# Power.net
KiCad netlist of a schematic drawn in Altium Designer
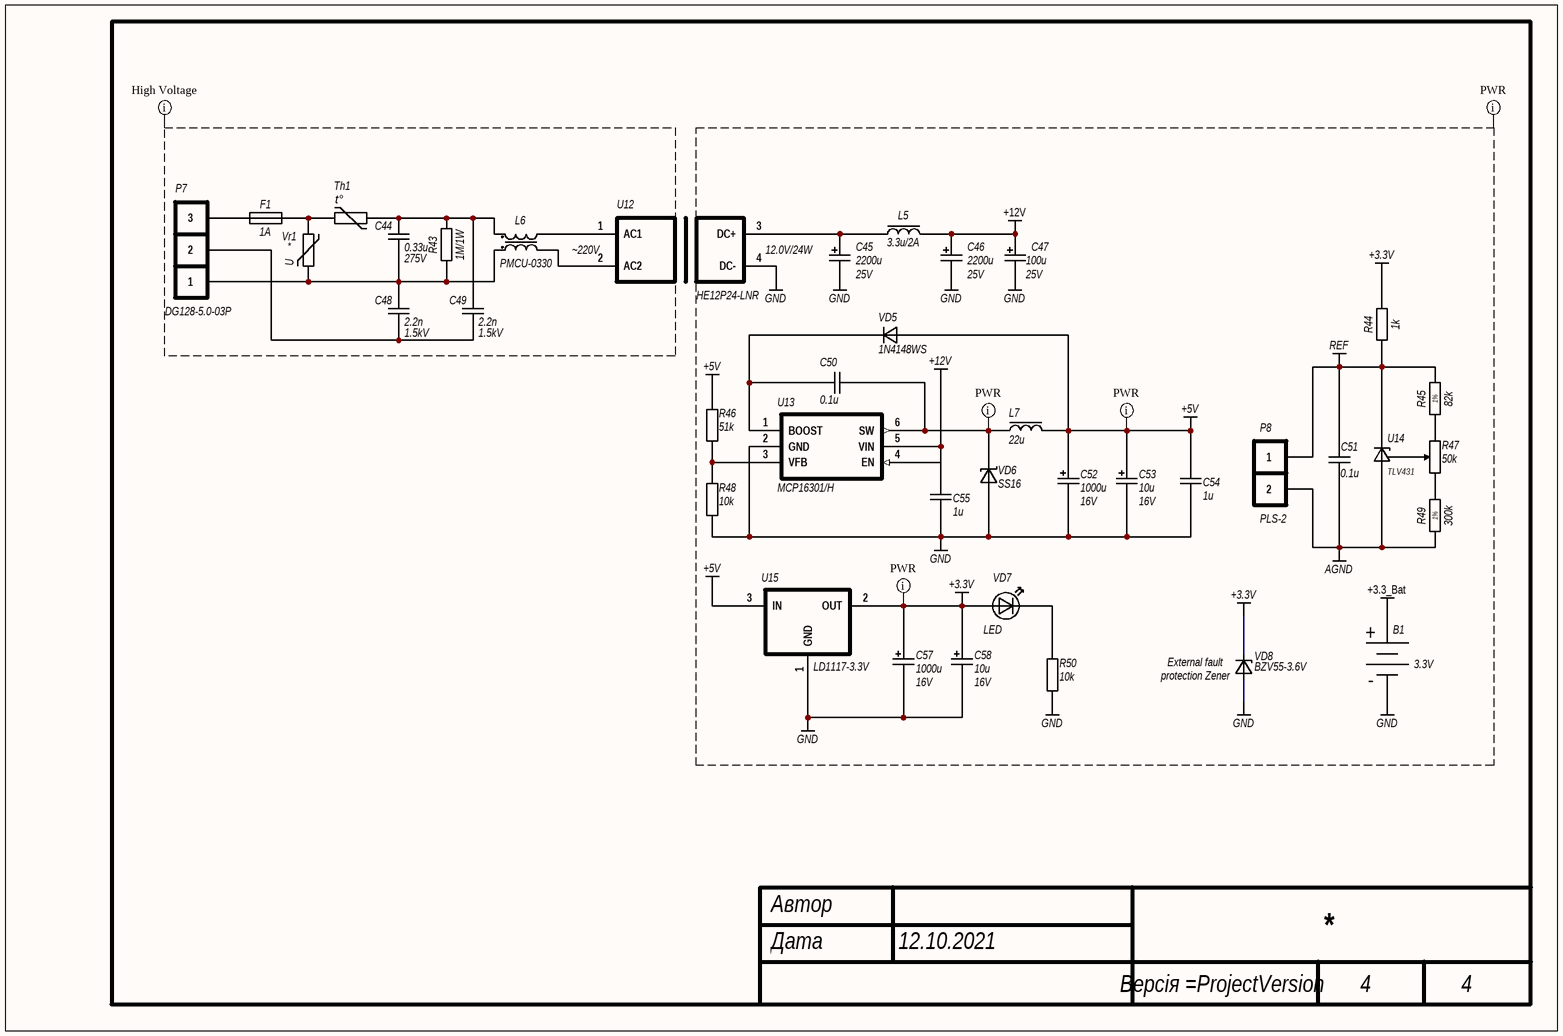
[diagram p0: Power.SchDoc]

(export (version "E")
  (design (tool "Eeschema 10.0.6"))
  (components
    (comp (ref "B1")
      (value "3.3V")
      (footprint "BH810")
      (description "Battery holder CR2032 (3.3В)")
      (libsource (lib "Passive") (part "Battery Holder"))
    )
    (comp (ref "C44")
      (value "0.33u")
      (footprint "MER 13x5.5 h10 R10.16")
      (fields (field (name "VOLTAGE") "275V"))
      (libsource (lib "Passive") (part "Capasitor"))
    )
    (comp (ref "C45")
      (value "2200u")
      (footprint "El-d13-h25-F5-0.6")
      (fields (field (name "VOLTAGE") "25V"))
      (libsource (lib "Passive") (part "Capasitor POL"))
    )
    (comp (ref "C46")
      (value "2200u")
      (footprint "El-d13-h25-F5-0.6")
      (fields (field (name "VOLTAGE") "25V"))
      (libsource (lib "Passive") (part "Capasitor POL"))
    )
    (comp (ref "C47")
      (value "100u")
      (footprint "EL Case A (3216-18)")
      (fields (field (name "VOLTAGE") "25V"))
      (libsource (lib "Passive") (part "Capasitor TECAP"))
    )
    (comp (ref "C48")
      (value "2.2n")
      (footprint "MER 13x5.5 h10 R10.16")
      (fields (field (name "VOLTAGE") "1.5kV"))
      (libsource (lib "Passive") (part "Capasitor"))
    )
    (comp (ref "C49")
      (value "2.2n")
      (footprint "MER 13x5.5 h10 R10.16")
      (fields (field (name "VOLTAGE") "1.5kV"))
      (libsource (lib "Passive") (part "Capasitor"))
    )
    (comp (ref "C50")
      (value "0.1u")
      (footprint "C0603(1608)")
      (libsource (lib "Passive") (part "Capasitor SMD"))
    )
    (comp (ref "C51")
      (value "0.1u")
      (footprint "C0603(1608)")
      (libsource (lib "Passive") (part "Capasitor SMD"))
    )
    (comp (ref "C52")
      (value "1000u")
      (footprint "El-d10-h16-F5-0.6")
      (fields (field (name "VOLTAGE") "16V"))
      (libsource (lib "Passive") (part "Capasitor POL"))
    )
    (comp (ref "C53")
      (value "10u")
      (footprint "EL Case A (3216-18)")
      (fields (field (name "VOLTAGE") "16V"))
      (libsource (lib "Passive") (part "Capasitor TECAP"))
    )
    (comp (ref "C54")
      (value "1u")
      (footprint "C0603(1608)")
      (libsource (lib "Passive") (part "Capasitor SMD"))
    )
    (comp (ref "C55")
      (value "1u")
      (footprint "C0603(1608)")
      (libsource (lib "Passive") (part "Capasitor SMD"))
    )
    (comp (ref "C57")
      (value "1000u")
      (footprint "El-d10-h16-F5-0.6")
      (fields (field (name "VOLTAGE") "16V"))
      (libsource (lib "Passive") (part "Capasitor POL"))
    )
    (comp (ref "C58")
      (value "10u")
      (footprint "EL Case A (3216-18)")
      (fields (field (name "VOLTAGE") "16V"))
      (libsource (lib "Passive") (part "Capasitor TECAP"))
    )
    (comp (ref "F1") (value "1A") (footprint "562 Series") (libsource (lib "Passive") (part "Fuse")))
    (comp (ref "L5") (value "3.3u/2A") (footprint "DR-CW8A") (libsource (lib "") (part "Inductor_1")))
    (comp (ref "L6") (value "~") (footprint "PMCU-0330") (libsource (lib "Passive") (part "Chocke Inductor")))
    (comp (ref "L7") (value "22u") (footprint "CDRH6D28") (libsource (lib "Passive") (part "Inductor")))
    (comp (ref "P7")
      (value "DG128-5.0-03P")
      (footprint "DG128-5.0-03P")
      (description "20A/300V AC 5mm")
      (libsource (lib "Connector") (part "DG128-5.0-03P"))
    )
    (comp (ref "P8") (value "PLS-2") (footprint "PLS-2") (libsource (lib "Connector") (part "PLS-2")))
    (comp (ref "R43")
      (value "1M/1W")
      (footprint "RES1016-650X250")
      (libsource (lib "Passive") (part "Resistor THD"))
    )
    (comp (ref "R44") (value "1k") (footprint "R0603") (libsource (lib "Passive") (part "Resistor SMD")))
    (comp (ref "R45")
      (value "82k")
      (footprint "R0603")
      (fields (field (name "ACCURACY") "1%"))
      (libsource (lib "Passive") (part "Resistor SMD"))
    )
    (comp (ref "R46") (value "51k") (footprint "R0603") (libsource (lib "Passive") (part "Resistor SMD")))
    (comp (ref "R47")
      (value "50k")
      (footprint "T910W (3296W)")
      (libsource (lib "Passive") (part "Trimming Resistor"))
    )
    (comp (ref "R48") (value "10k") (footprint "R0603") (libsource (lib "Passive") (part "Resistor SMD")))
    (comp (ref "R49")
      (value "300k")
      (footprint "R0603")
      (fields (field (name "ACCURACY") "1%"))
      (libsource (lib "Passive") (part "Resistor SMD"))
    )
    (comp (ref "R50") (value "10k") (footprint "R0603") (libsource (lib "Passive") (part "Resistor SMD")))
    (comp (ref "Th1") (value "~") (footprint "TH D13 7.5b") (libsource (lib "Passive") (part "Thermistor")))
    (comp (ref "U12")
      (value "HE12P24-LNR")
      (footprint "HExxPyy-LRN")
      (fields (field (name "OUT") "12.0V/24W") (field (name "IN") "~220V"))
      (libsource (lib "Power") (part "HE12P24-LNR"))
    )
    (comp (ref "U13")
      (value "MCP16301/H")
      (footprint "SOT23-6")
      (libsource (lib "Power") (part "MCP16301/H"))
    )
    (comp (ref "U14") (value "TLV431") (footprint "SOT23") (libsource (lib "Diode") (part "TLV431")))
    (comp (ref "U15") (value "LD1117-3.3V") (footprint "SOT223") (libsource (lib "Power") (part "LD1117")))
    (comp (ref "VD5")
      (value "1N4148WS")
      (footprint "SOD323")
      (description "SOD323 100V 200mA")
      (libsource (lib "Diode") (part "1N4148WS"))
    )
    (comp (ref "VD6")
      (value "SS16")
      (footprint "DO-214AC (SMA)")
      (description "SMA (DO214AC) Schottky 60V 1A")
      (libsource (lib "Diode") (part "SS16"))
    )
    (comp (ref "VD7") (value "LED") (footprint "SMD_0805_GREEN") (libsource (lib "Diode") (part "LED")))
    (comp (ref "VD8")
      (value "BZV55-3.6V")
      (footprint "SOD80C")
      (description "SOD80C 250mA")
      (fields (field (name "VOLTAGE") "3.6V"))
      (libsource (lib "Diode") (part "BZV55"))
    )
    (comp (ref "Vr1") (value "*") (footprint "VAR-10K-5.6") (libsource (lib "Passive") (part "Varistor")))
  )
  (nets
    (net (code "1") (name "+3.3V") (class "Default")
      (node (ref "C57") (pin "1") (pinfunction "1_1") (pintype "passive"))
      (node (ref "C58") (pin "1") (pinfunction "1_1") (pintype "passive"))
      (node (ref "R44") (pin "2") (pinfunction "2_2") (pintype "passive"))
      (node (ref "U15") (pin "2") (pinfunction "OUT_2") (pintype "power_in"))
      (node (ref "VD7") (pin "1") (pinfunction "A_1") (pintype "passive"))
      (node (ref "VD8") (pin "2") (pinfunction "K_2") (pintype "passive"))
    )
    (net (code "2") (name "+3.3_Bat") (class "Default")
      (node (ref "B1") (pin "1") (pinfunction "1_1") (pintype "passive"))
    )
    (net (code "3") (name "+5V") (class "Default")
      (node (ref "C52") (pin "1") (pinfunction "1_1") (pintype "passive"))
      (node (ref "C53") (pin "1") (pinfunction "1_1") (pintype "passive"))
      (node (ref "C54") (pin "1") (pinfunction "1_1") (pintype "passive"))
      (node (ref "L7") (pin "2") (pinfunction "2_2") (pintype "passive"))
      (node (ref "R46") (pin "2") (pinfunction "2_2") (pintype "passive"))
      (node (ref "U15") (pin "3") (pinfunction "IN_3") (pintype "power_in"))
      (node (ref "VD5") (pin "1") (pinfunction "A_1") (pintype "passive"))
    )
    (net (code "4") (name "+12V") (class "Default")
      (node (ref "C46") (pin "1") (pinfunction "1_1") (pintype "passive"))
      (node (ref "C47") (pin "1") (pinfunction "1_1") (pintype "passive"))
      (node (ref "C55") (pin "1") (pinfunction "1_1") (pintype "passive"))
      (node (ref "L5") (pin "2") (pinfunction "2_2") (pintype "passive"))
      (node (ref "U13") (pin "4") (pinfunction "EN_4") (pintype "input"))
      (node (ref "U13") (pin "5") (pinfunction "VIN_5") (pintype "power_in"))
    )
    (net (code "5") (name "AGND") (class "Default")
      (node (ref "C51") (pin "1") (pinfunction "1_1") (pintype "passive"))
      (node (ref "P8") (pin "2") (pinfunction "2_2") (pintype "passive"))
      (node (ref "R49") (pin "1") (pinfunction "1_1") (pintype "passive"))
      (node (ref "U14") (pin "3") (pinfunction "A_3") (pintype "passive"))
    )
    (net (code "6") (name "GND") (class "Default")
      (node (ref "B1") (pin "2") (pinfunction "2_2") (pintype "passive"))
      (node (ref "C45") (pin "2") (pinfunction "2_2") (pintype "passive"))
      (node (ref "C46") (pin "2") (pinfunction "2_2") (pintype "passive"))
      (node (ref "C47") (pin "2") (pinfunction "2_2") (pintype "passive"))
      (node (ref "C52") (pin "2") (pinfunction "2_2") (pintype "passive"))
      (node (ref "C53") (pin "2") (pinfunction "2_2") (pintype "passive"))
      (node (ref "C54") (pin "2") (pinfunction "2_2") (pintype "passive"))
      (node (ref "C55") (pin "2") (pinfunction "2_2") (pintype "passive"))
      (node (ref "C57") (pin "2") (pinfunction "2_2") (pintype "passive"))
      (node (ref "C58") (pin "2") (pinfunction "2_2") (pintype "passive"))
      (node (ref "R48") (pin "1") (pinfunction "1_1") (pintype "passive"))
      (node (ref "R50") (pin "1") (pinfunction "1_1") (pintype "passive"))
      (node (ref "U12") (pin "4") (pinfunction "DC-_4") (pintype "passive"))
      (node (ref "U13") (pin "2") (pinfunction "GND_2") (pintype "power_in"))
      (node (ref "U15") (pin "1") (pinfunction "GND_1") (pintype "power_in"))
      (node (ref "VD6") (pin "1") (pinfunction "A_1") (pintype "passive"))
      (node (ref "VD8") (pin "1") (pinfunction "A_1") (pintype "passive"))
    )
    (net (code "7") (name "Net-(C44-Pad1)") (class "Default")
      (node (ref "C44") (pin "1") (pinfunction "1_1") (pintype "passive"))
      (node (ref "C48") (pin "2") (pinfunction "2_2") (pintype "passive"))
      (node (ref "L6") (pin "2") (pinfunction "2_2") (pintype "passive"))
      (node (ref "P7") (pin "1") (pinfunction "1_1") (pintype "passive"))
      (node (ref "R43") (pin "1") (pinfunction "1_1") (pintype "passive"))
      (node (ref "Vr1") (pin "1") (pinfunction "1_1") (pintype "passive"))
    )
    (net (code "8") (name "Net-(C44-Pad2)") (class "Default")
      (node (ref "C44") (pin "2") (pinfunction "2_2") (pintype "passive"))
      (node (ref "C49") (pin "2") (pinfunction "2_2") (pintype "passive"))
      (node (ref "L6") (pin "1") (pinfunction "1_1") (pintype "passive"))
      (node (ref "R43") (pin "2") (pinfunction "2_2") (pintype "passive"))
      (node (ref "Th1") (pin "2") (pinfunction "2_2") (pintype "passive"))
    )
    (net (code "9") (name "Net-(C48-Pad1)") (class "Default")
      (node (ref "C48") (pin "1") (pinfunction "1_1") (pintype "passive"))
      (node (ref "C49") (pin "1") (pinfunction "1_1") (pintype "passive"))
      (node (ref "P7") (pin "2") (pinfunction "2_2") (pintype "passive"))
    )
    (net (code "10") (name "Net-(F1-Pad1)") (class "Default")
      (node (ref "F1") (pin "1") (pinfunction "1_1") (pintype "passive"))
      (node (ref "P7") (pin "3") (pinfunction "3_3") (pintype "passive"))
    )
    (net (code "11") (name "Net-(F1-Pad2)") (class "Default")
      (node (ref "F1") (pin "2") (pinfunction "2_2") (pintype "passive"))
      (node (ref "Th1") (pin "1") (pinfunction "1_1") (pintype "passive"))
      (node (ref "Vr1") (pin "2") (pinfunction "2_2") (pintype "passive"))
    )
    (net (code "12") (name "Net-(R45-Pad1)") (class "Default")
      (node (ref "R45") (pin "1") (pinfunction "1_1") (pintype "passive"))
      (node (ref "R47") (pin "3") (pinfunction "3_3") (pintype "passive"))
    )
    (net (code "13") (name "Net-(R47-Pad1)") (class "Default")
      (node (ref "R47") (pin "1") (pinfunction "1_1") (pintype "passive"))
      (node (ref "R49") (pin "2") (pinfunction "2_2") (pintype "passive"))
    )
    (net (code "14") (name "Net-(U12-AC1)") (class "Default")
      (node (ref "L6") (pin "4") (pinfunction "4_4") (pintype "passive"))
      (node (ref "U12") (pin "1") (pinfunction "AC1_1") (pintype "passive"))
    )
    (net (code "15") (name "Net-(U12-AC2)") (class "Default")
      (node (ref "L6") (pin "3") (pinfunction "3_3") (pintype "passive"))
      (node (ref "U12") (pin "2") (pinfunction "AC2_2") (pintype "passive"))
    )
    (net (code "16") (name "Net-(U12-DC+)") (class "Default")
      (node (ref "C45") (pin "1") (pinfunction "1_1") (pintype "passive"))
      (node (ref "L5") (pin "1") (pinfunction "1_1") (pintype "passive"))
      (node (ref "U12") (pin "3") (pinfunction "DC+_3") (pintype "passive"))
    )
    (net (code "17") (name "Net-(U13-BOOST)") (class "Default")
      (node (ref "C50") (pin "1") (pinfunction "1_1") (pintype "passive"))
      (node (ref "U13") (pin "1") (pinfunction "BOOST_1") (pintype "passive"))
      (node (ref "VD5") (pin "2") (pinfunction "K_2") (pintype "passive"))
    )
    (net (code "18") (name "Net-(U13-SW)") (class "Default")
      (node (ref "C50") (pin "2") (pinfunction "2_2") (pintype "passive"))
      (node (ref "L7") (pin "1") (pinfunction "1_1") (pintype "passive"))
      (node (ref "U13") (pin "6") (pinfunction "SW_6") (pintype "output"))
      (node (ref "VD6") (pin "2") (pinfunction "K_2") (pintype "passive"))
    )
    (net (code "19") (name "Net-(U13-VFB)") (class "Default")
      (node (ref "R46") (pin "1") (pinfunction "1_1") (pintype "passive"))
      (node (ref "R48") (pin "2") (pinfunction "2_2") (pintype "passive"))
      (node (ref "U13") (pin "3") (pinfunction "VFB_3") (pintype "passive"))
    )
    (net (code "20") (name "Net-(U14-Adj)") (class "Default")
      (node (ref "R47") (pin "2") (pinfunction "2_2") (pintype "passive"))
      (node (ref "U14") (pin "1") (pinfunction "Adj_1") (pintype "passive"))
    )
    (net (code "21") (name "Net-(VD7-K)") (class "Default")
      (node (ref "R50") (pin "2") (pinfunction "2_2") (pintype "passive"))
      (node (ref "VD7") (pin "2") (pinfunction "K_2") (pintype "passive"))
    )
    (net (code "22") (name "REF") (class "Default")
      (node (ref "C51") (pin "2") (pinfunction "2_2") (pintype "passive"))
      (node (ref "P8") (pin "1") (pinfunction "1_1") (pintype "passive"))
      (node (ref "R44") (pin "1") (pinfunction "1_1") (pintype "passive"))
      (node (ref "R45") (pin "2") (pinfunction "2_2") (pintype "passive"))
      (node (ref "U14") (pin "2") (pinfunction "K_2") (pintype "passive"))
    )
  )
)
